# Bakelite_Interface_Board_v1_1.net
KiCad netlist of a schematic drawn in EAGLE
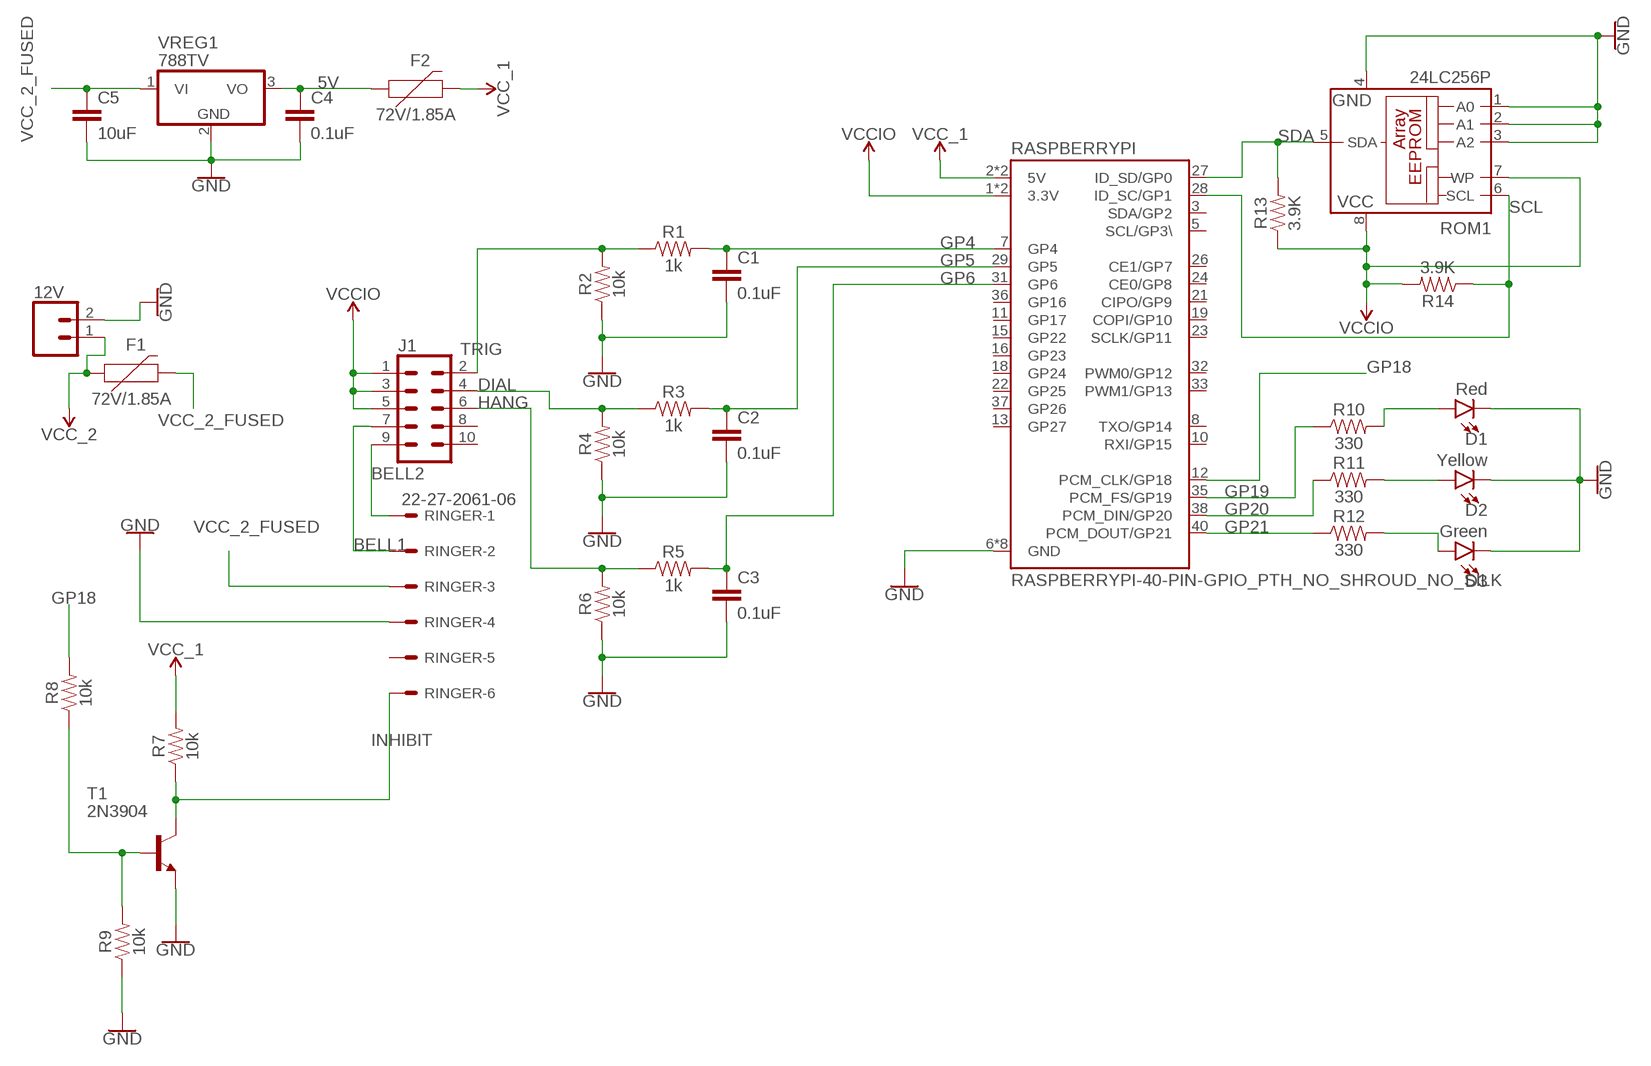
[diagram p0: schematic, sheet 1]

(export (version "E")
  (design (tool "Eeschema 10.0.6"))
  (components
    (comp (ref "12V")
      (value "CONN_025MM")
      (footprint "eagle-import:SCREWTERMINAL-5MM-2")
      (libsource (lib "eagle-import") (part "CONN_025MM"))
    )
    (comp (ref "C1")
      (value "0.1uF")
      (footprint "eagle-import:CAP-PTH-SMALL-KIT")
      (libsource (lib "eagle-import") (part "0.1UF-KIT-EZ-50V-20%"))
    )
    (comp (ref "C2")
      (value "0.1uF")
      (footprint "eagle-import:CAP-PTH-SMALL-KIT")
      (libsource (lib "eagle-import") (part "0.1UF-KIT-EZ-50V-20%"))
    )
    (comp (ref "C3")
      (value "0.1uF")
      (footprint "eagle-import:CAP-PTH-SMALL-KIT")
      (libsource (lib "eagle-import") (part "0.1UF-KIT-EZ-50V-20%"))
    )
    (comp (ref "C4")
      (value "0.1uF")
      (footprint "eagle-import:CAP-PTH-SMALL-KIT")
      (libsource (lib "eagle-import") (part "0.1UF-KIT-EZ-50V-20%"))
    )
    (comp (ref "C5")
      (value "10uF")
      (footprint "eagle-import:CAP-PTH-SMALL-KIT")
      (libsource (lib "eagle-import") (part "0.1UF-KIT-EZ-50V-20%"))
    )
    (comp (ref "D1")
      (value "Red")
      (footprint "eagle-import:LED_5MM")
      (libsource (lib "eagle-import") (part "LED5MM"))
    )
    (comp (ref "D2")
      (value "Yellow")
      (footprint "eagle-import:LED_5MM")
      (libsource (lib "eagle-import") (part "LED5MM"))
    )
    (comp (ref "D3")
      (value "Green")
      (footprint "eagle-import:LED_5MM")
      (libsource (lib "eagle-import") (part "LED5MM"))
    )
    (comp (ref "F1")
      (value "72V/1.85A")
      (footprint "eagle-import:PTH")
      (libsource (lib "eagle-import") (part "PPTC_PTH"))
    )
    (comp (ref "F2")
      (value "72V/1.85A")
      (footprint "eagle-import:PTH")
      (libsource (lib "eagle-import") (part "PPTC_PTH"))
    )
    (comp (ref "J1")
      (value "CONN_05X2PTH")
      (footprint "eagle-import:2X5")
      (libsource (lib "eagle-import") (part "CONN_05X2PTH"))
    )
    (comp (ref "R1")
      (value "1k")
      (footprint "eagle-import:AXIAL-0.3")
      (libsource (lib "eagle-import") (part "1KOHM-HORIZ-1/4W-5%"))
    )
    (comp (ref "R2")
      (value "10k")
      (footprint "eagle-import:AXIAL-0.3")
      (libsource (lib "eagle-import") (part "10KOHM-HORIZ-1/4W-5%"))
    )
    (comp (ref "R3")
      (value "1k")
      (footprint "eagle-import:AXIAL-0.3")
      (libsource (lib "eagle-import") (part "1KOHM-HORIZ-1/4W-5%"))
    )
    (comp (ref "R4")
      (value "10k")
      (footprint "eagle-import:AXIAL-0.3")
      (libsource (lib "eagle-import") (part "10KOHM-HORIZ-1/4W-5%"))
    )
    (comp (ref "R5")
      (value "1k")
      (footprint "eagle-import:AXIAL-0.3")
      (libsource (lib "eagle-import") (part "1KOHM-HORIZ-1/4W-5%"))
    )
    (comp (ref "R6")
      (value "10k")
      (footprint "eagle-import:AXIAL-0.3")
      (libsource (lib "eagle-import") (part "10KOHM-HORIZ-1/4W-5%"))
    )
    (comp (ref "R7")
      (value "10k")
      (footprint "eagle-import:AXIAL-0.3")
      (libsource (lib "eagle-import") (part "10KOHM-HORIZ-1/4W-5%"))
    )
    (comp (ref "R8")
      (value "10k")
      (footprint "eagle-import:AXIAL-0.3")
      (libsource (lib "eagle-import") (part "10KOHM-HORIZ-1/4W-5%"))
    )
    (comp (ref "R9")
      (value "10k")
      (footprint "eagle-import:AXIAL-0.3")
      (libsource (lib "eagle-import") (part "10KOHM-HORIZ-1/4W-5%"))
    )
    (comp (ref "R10")
      (value "330")
      (footprint "eagle-import:AXIAL-0.3")
      (libsource (lib "eagle-import") (part "330OHM-HORIZ-1/10W-5%"))
    )
    (comp (ref "R11")
      (value "330")
      (footprint "eagle-import:AXIAL-0.3")
      (libsource (lib "eagle-import") (part "330OHM-HORIZ-1/10W-5%"))
    )
    (comp (ref "R12")
      (value "330")
      (footprint "eagle-import:AXIAL-0.3")
      (libsource (lib "eagle-import") (part "330OHM-HORIZ-1/10W-5%"))
    )
    (comp (ref "R13")
      (value "3.9K")
      (footprint "eagle-import:AXIAL-0.3")
      (libsource (lib "eagle-import") (part "RESISTORAXIAL-0.3"))
    )
    (comp (ref "R14")
      (value "3.9K")
      (footprint "eagle-import:AXIAL-0.3")
      (libsource (lib "eagle-import") (part "RESISTORAXIAL-0.3"))
    )
    (comp (ref "RASPBERRYPI")
      (value "RASPBERRYPI-40-PIN-GPIO_PTH_NO_SHROUD_NO_SILK")
      (footprint "eagle-import:2X20_NOSILK")
      (libsource (lib "eagle-import") (part "RASPBERRYPI-40-PIN-GPIO_PTH_NO_SHROUD_NO_SILK"))
    )
    (comp (ref "RINGER")
      (value "22-27-2061-06")
      (footprint "eagle-import:6410-06")
      (fields (field (name "MF") "MOLEX"))
      (libsource (lib "eagle-import") (part "22-?-0627-2061"))
    )
    (comp (ref "ROM1")
      (value "24LC256P")
      (footprint "eagle-import:DIL8")
      (fields (field (name "MF") "MICROCHIP") (field (name "MPN") "24LC256-E/P"))
      (libsource (lib "eagle-import") (part "24PLC256"))
    )
    (comp (ref "T1")
      (value "2N3904")
      (footprint "eagle-import:TO92")
      (libsource (lib "eagle-import") (part "2N3904"))
    )
    (comp (ref "VREG1")
      (value "788TV")
      (footprint "eagle-import:TO220V")
      (libsource (lib "eagle-import") (part "78TV8"))
    )
  )
  (nets
    (net (code "1") (name "/5V") (class "Default")
      (node (ref "C4") (pin "1") (pinfunction "1_1") (pintype "passive"))
      (node (ref "F2") (pin "P$1") (pinfunction "1_P$1") (pintype "bidirectional"))
      (node (ref "VREG1") (pin "3") (pinfunction "VO_3") (pintype "passive"))
    )
    (net (code "2") (name "/BELL1") (class "Default")
      (node (ref "J1") (pin "7") (pinfunction "7_7") (pintype "passive"))
      (node (ref "RINGER") (pin "2") (pinfunction "S_2") (pintype "passive"))
    )
    (net (code "3") (name "/BELL2") (class "Default")
      (node (ref "J1") (pin "9") (pinfunction "9_9") (pintype "passive"))
      (node (ref "RINGER") (pin "1") (pinfunction "S_1") (pintype "passive"))
    )
    (net (code "4") (name "/DIAL") (class "Default")
      (node (ref "J1") (pin "4") (pinfunction "4_4") (pintype "passive"))
      (node (ref "R3") (pin "P$1") (pinfunction "1_P$1") (pintype "passive"))
      (node (ref "R4") (pin "P$2") (pinfunction "2_P$2") (pintype "passive"))
    )
    (net (code "5") (name "/GP4") (class "Default")
      (node (ref "C1") (pin "1") (pinfunction "1_1") (pintype "passive"))
      (node (ref "R1") (pin "P$2") (pinfunction "2_P$2") (pintype "passive"))
      (node (ref "RASPBERRYPI") (pin "7") (pinfunction "GP4_7") (pintype "bidirectional"))
    )
    (net (code "6") (name "/GP5") (class "Default")
      (node (ref "C2") (pin "1") (pinfunction "1_1") (pintype "passive"))
      (node (ref "R3") (pin "P$2") (pinfunction "2_P$2") (pintype "passive"))
      (node (ref "RASPBERRYPI") (pin "29") (pinfunction "GP5_29") (pintype "bidirectional"))
    )
    (net (code "7") (name "/GP6") (class "Default")
      (node (ref "C3") (pin "1") (pinfunction "1_1") (pintype "passive"))
      (node (ref "R5") (pin "P$2") (pinfunction "2_P$2") (pintype "passive"))
      (node (ref "RASPBERRYPI") (pin "31") (pinfunction "GP6_31") (pintype "bidirectional"))
    )
    (net (code "8") (name "/GP18") (class "Default")
      (node (ref "R8") (pin "P$2") (pinfunction "2_P$2") (pintype "passive"))
      (node (ref "RASPBERRYPI") (pin "12") (pinfunction "PCM_CLK/GP18_12") (pintype "bidirectional"))
    )
    (net (code "9") (name "/GP19") (class "Default")
      (node (ref "R10") (pin "P$1") (pinfunction "1_P$1") (pintype "passive"))
      (node (ref "RASPBERRYPI") (pin "35") (pinfunction "PCM_FS/GP19_35") (pintype "bidirectional"))
    )
    (net (code "10") (name "/GP20") (class "Default")
      (node (ref "R11") (pin "P$1") (pinfunction "1_P$1") (pintype "passive"))
      (node (ref "RASPBERRYPI") (pin "38") (pinfunction "PCM_DIN/GP20_38") (pintype "bidirectional"))
    )
    (net (code "11") (name "/GP21") (class "Default")
      (node (ref "R12") (pin "P$1") (pinfunction "1_P$1") (pintype "passive"))
      (node (ref "RASPBERRYPI") (pin "40") (pinfunction "PCM_DOUT/GP21_40") (pintype "bidirectional"))
    )
    (net (code "12") (name "/HANG") (class "Default")
      (node (ref "J1") (pin "6") (pinfunction "6_6") (pintype "passive"))
      (node (ref "R5") (pin "P$1") (pinfunction "1_P$1") (pintype "passive"))
      (node (ref "R6") (pin "P$2") (pinfunction "2_P$2") (pintype "passive"))
    )
    (net (code "13") (name "/INHIBIT") (class "Default")
      (node (ref "R7") (pin "P$1") (pinfunction "1_P$1") (pintype "passive"))
      (node (ref "RINGER") (pin "6") (pinfunction "S_6") (pintype "passive"))
      (node (ref "T1") (pin "1") (pinfunction "C_1") (pintype "passive"))
    )
    (net (code "14") (name "/SCL") (class "Default")
      (node (ref "R14") (pin "P$1") (pinfunction "1_P$1") (pintype "passive"))
      (node (ref "RASPBERRYPI") (pin "28") (pinfunction "ID_SC/GP1_28") (pintype "bidirectional"))
      (node (ref "ROM1") (pin "6") (pinfunction "SCL_6") (pintype "input"))
    )
    (net (code "15") (name "/SDA") (class "Default")
      (node (ref "R13") (pin "P$2") (pinfunction "2_P$2") (pintype "passive"))
      (node (ref "RASPBERRYPI") (pin "27") (pinfunction "ID_SD/GP0_27") (pintype "bidirectional"))
      (node (ref "ROM1") (pin "5") (pinfunction "SDA_5") (pintype "bidirectional"))
    )
    (net (code "16") (name "/TRIG") (class "Default")
      (node (ref "J1") (pin "2") (pinfunction "2_2") (pintype "passive"))
      (node (ref "R1") (pin "P$1") (pinfunction "1_P$1") (pintype "passive"))
      (node (ref "R2") (pin "P$2") (pinfunction "2_P$2") (pintype "passive"))
    )
    (net (code "17") (name "/VCC_2_FUSED") (class "Default")
      (node (ref "C5") (pin "1") (pinfunction "1_1") (pintype "passive"))
      (node (ref "F1") (pin "P$2") (pinfunction "2_P$2") (pintype "bidirectional"))
      (node (ref "RINGER") (pin "3") (pinfunction "S_3") (pintype "passive"))
      (node (ref "VREG1") (pin "1") (pinfunction "VI_1") (pintype "input"))
    )
    (net (code "18") (name "GND") (class "Default")
      (node (ref "12V") (pin "2") (pinfunction "2_2") (pintype "passive"))
      (node (ref "C1") (pin "2") (pinfunction "2_2") (pintype "passive"))
      (node (ref "C2") (pin "2") (pinfunction "2_2") (pintype "passive"))
      (node (ref "C3") (pin "2") (pinfunction "2_2") (pintype "passive"))
      (node (ref "C4") (pin "2") (pinfunction "2_2") (pintype "passive"))
      (node (ref "C5") (pin "2") (pinfunction "2_2") (pintype "passive"))
      (node (ref "D1") (pin "K") (pinfunction "C_K") (pintype "passive"))
      (node (ref "D2") (pin "K") (pinfunction "C_K") (pintype "passive"))
      (node (ref "D3") (pin "K") (pinfunction "C_K") (pintype "passive"))
      (node (ref "R2") (pin "P$1") (pinfunction "1_P$1") (pintype "passive"))
      (node (ref "R4") (pin "P$1") (pinfunction "1_P$1") (pintype "passive"))
      (node (ref "R6") (pin "P$1") (pinfunction "1_P$1") (pintype "passive"))
      (node (ref "R9") (pin "P$1") (pinfunction "1_P$1") (pintype "passive"))
      (node (ref "RASPBERRYPI") (pin "14") (pinfunction "GND_14") (pintype "power_in"))
      (node (ref "RASPBERRYPI") (pin "20") (pinfunction "GND_20") (pintype "power_in"))
      (node (ref "RASPBERRYPI") (pin "25") (pinfunction "GND_25") (pintype "power_in"))
      (node (ref "RASPBERRYPI") (pin "30") (pinfunction "GND_30") (pintype "power_in"))
      (node (ref "RASPBERRYPI") (pin "34") (pinfunction "GND_34") (pintype "power_in"))
      (node (ref "RASPBERRYPI") (pin "39") (pinfunction "GND_39") (pintype "power_in"))
      (node (ref "RASPBERRYPI") (pin "6") (pinfunction "GND_6") (pintype "power_in"))
      (node (ref "RASPBERRYPI") (pin "9") (pinfunction "GND_9") (pintype "power_in"))
      (node (ref "RINGER") (pin "4") (pinfunction "S_4") (pintype "passive"))
      (node (ref "ROM1") (pin "1") (pinfunction "A0_1") (pintype "input"))
      (node (ref "ROM1") (pin "2") (pinfunction "A1_2") (pintype "input"))
      (node (ref "ROM1") (pin "3") (pinfunction "A2_3") (pintype "input"))
      (node (ref "ROM1") (pin "4") (pinfunction "GND_4") (pintype "power_in"))
      (node (ref "T1") (pin "3") (pinfunction "E_3") (pintype "passive"))
      (node (ref "VREG1") (pin "2") (pinfunction "GND_2") (pintype "passive"))
    )
    (net (code "19") (name "Net-(R8-1)") (class "Default")
      (node (ref "R8") (pin "P$1") (pinfunction "1_P$1") (pintype "passive"))
      (node (ref "R9") (pin "P$2") (pinfunction "2_P$2") (pintype "passive"))
      (node (ref "T1") (pin "2") (pinfunction "B_2") (pintype "passive"))
    )
    (net (code "20") (name "Net-(R10-2)") (class "Default")
      (node (ref "D1") (pin "A") (pinfunction "A_A") (pintype "passive"))
      (node (ref "R10") (pin "P$2") (pinfunction "2_P$2") (pintype "passive"))
    )
    (net (code "21") (name "Net-(R11-2)") (class "Default")
      (node (ref "D2") (pin "A") (pinfunction "A_A") (pintype "passive"))
      (node (ref "R11") (pin "P$2") (pinfunction "2_P$2") (pintype "passive"))
    )
    (net (code "22") (name "Net-(R12-2)") (class "Default")
      (node (ref "D3") (pin "A") (pinfunction "A_A") (pintype "passive"))
      (node (ref "R12") (pin "P$2") (pinfunction "2_P$2") (pintype "passive"))
    )
    (net (code "23") (name "VCCIO") (class "Default")
      (node (ref "J1") (pin "1") (pinfunction "1_1") (pintype "passive"))
      (node (ref "J1") (pin "3") (pinfunction "3_3") (pintype "passive"))
      (node (ref "J1") (pin "5") (pinfunction "5_5") (pintype "passive"))
      (node (ref "R13") (pin "P$1") (pinfunction "1_P$1") (pintype "passive"))
      (node (ref "R14") (pin "P$2") (pinfunction "2_P$2") (pintype "passive"))
      (node (ref "RASPBERRYPI") (pin "1") (pinfunction "3.3V_1") (pintype "power_in"))
      (node (ref "RASPBERRYPI") (pin "17") (pinfunction "3.3V_17") (pintype "power_in"))
      (node (ref "ROM1") (pin "7") (pinfunction "WP_7") (pintype "input"))
      (node (ref "ROM1") (pin "8") (pinfunction "VCC_8") (pintype "power_in"))
    )
    (net (code "24") (name "VCC_1") (class "Default")
      (node (ref "F2") (pin "P$2") (pinfunction "2_P$2") (pintype "bidirectional"))
      (node (ref "R7") (pin "P$2") (pinfunction "2_P$2") (pintype "passive"))
      (node (ref "RASPBERRYPI") (pin "2") (pinfunction "5V_2") (pintype "power_in"))
      (node (ref "RASPBERRYPI") (pin "4") (pinfunction "5V_4") (pintype "power_in"))
    )
    (net (code "25") (name "VCC_2") (class "Default")
      (node (ref "12V") (pin "1") (pinfunction "1_1") (pintype "passive"))
      (node (ref "F1") (pin "P$1") (pinfunction "1_P$1") (pintype "bidirectional"))
    )
    (net (code "26") (name "unconnected-(J1-Pad8)") (class "Default")
      (node (ref "J1") (pin "8") (pinfunction "8_8") (pintype "passive"))
    )
    (net (code "27") (name "unconnected-(J1-Pad10)") (class "Default")
      (node (ref "J1") (pin "10") (pinfunction "10_10") (pintype "passive"))
    )
    (net (code "28") (name "unconnected-(RASPBERRYPI-CE0{slash}GP8-Pad24)") (class "Default")
      (node (ref "RASPBERRYPI") (pin "24") (pinfunction "CE0/GP8_24") (pintype "output"))
    )
    (net (code "29") (name "unconnected-(RASPBERRYPI-CE1{slash}GP7-Pad26)") (class "Default")
      (node (ref "RASPBERRYPI") (pin "26") (pinfunction "CE1/GP7_26") (pintype "output"))
    )
    (net (code "30") (name "unconnected-(RASPBERRYPI-CIPO{slash}GP9-Pad21)") (class "Default")
      (node (ref "RASPBERRYPI") (pin "21") (pinfunction "CIPO/GP9_21") (pintype "input"))
    )
    (net (code "31") (name "unconnected-(RASPBERRYPI-COPI{slash}GP10-Pad19)") (class "Default")
      (node (ref "RASPBERRYPI") (pin "19") (pinfunction "COPI/GP10_19") (pintype "output"))
    )
    (net (code "32") (name "unconnected-(RASPBERRYPI-GP16-Pad36)") (class "Default")
      (node (ref "RASPBERRYPI") (pin "36") (pinfunction "GP16_36") (pintype "bidirectional"))
    )
    (net (code "33") (name "unconnected-(RASPBERRYPI-GP17-Pad11)") (class "Default")
      (node (ref "RASPBERRYPI") (pin "11") (pinfunction "GP17_11") (pintype "bidirectional"))
    )
    (net (code "34") (name "unconnected-(RASPBERRYPI-GP22-Pad15)") (class "Default")
      (node (ref "RASPBERRYPI") (pin "15") (pinfunction "GP22_15") (pintype "bidirectional"))
    )
    (net (code "35") (name "unconnected-(RASPBERRYPI-GP23-Pad16)") (class "Default")
      (node (ref "RASPBERRYPI") (pin "16") (pinfunction "GP23_16") (pintype "bidirectional"))
    )
    (net (code "36") (name "unconnected-(RASPBERRYPI-GP24-Pad18)") (class "Default")
      (node (ref "RASPBERRYPI") (pin "18") (pinfunction "GP24_18") (pintype "bidirectional"))
    )
    (net (code "37") (name "unconnected-(RASPBERRYPI-GP25-Pad22)") (class "Default")
      (node (ref "RASPBERRYPI") (pin "22") (pinfunction "GP25_22") (pintype "bidirectional"))
    )
    (net (code "38") (name "unconnected-(RASPBERRYPI-GP26-Pad37)") (class "Default")
      (node (ref "RASPBERRYPI") (pin "37") (pinfunction "GP26_37") (pintype "bidirectional"))
    )
    (net (code "39") (name "unconnected-(RASPBERRYPI-GP27-Pad13)") (class "Default")
      (node (ref "RASPBERRYPI") (pin "13") (pinfunction "GP27_13") (pintype "bidirectional"))
    )
    (net (code "40") (name "unconnected-(RASPBERRYPI-PWM0{slash}GP12-Pad32)") (class "Default")
      (node (ref "RASPBERRYPI") (pin "32") (pinfunction "PWM0/GP12_32") (pintype "bidirectional"))
    )
    (net (code "41") (name "unconnected-(RASPBERRYPI-PWM1{slash}GP13-Pad33)") (class "Default")
      (node (ref "RASPBERRYPI") (pin "33") (pinfunction "PWM1/GP13_33") (pintype "bidirectional"))
    )
    (net (code "42") (name "unconnected-(RASPBERRYPI-RXI{slash}GP15-Pad10)") (class "Default")
      (node (ref "RASPBERRYPI") (pin "10") (pinfunction "RXI/GP15_10") (pintype "input"))
    )
    (net (code "43") (name "unconnected-(RASPBERRYPI-SCLK{slash}GP11-Pad23)") (class "Default")
      (node (ref "RASPBERRYPI") (pin "23") (pinfunction "SCLK/GP11_23") (pintype "output"))
    )
    (net (code "44") (name "unconnected-(RASPBERRYPI-SCL{slash}GP3\\-Pad5)") (class "Default")
      (node (ref "RASPBERRYPI") (pin "5") (pinfunction "SCL/GP3\\_5") (pintype "bidirectional"))
    )
    (net (code "45") (name "unconnected-(RASPBERRYPI-SDA{slash}GP2-Pad3)") (class "Default")
      (node (ref "RASPBERRYPI") (pin "3") (pinfunction "SDA/GP2_3") (pintype "bidirectional"))
    )
    (net (code "46") (name "unconnected-(RASPBERRYPI-TXO{slash}GP14-Pad8)") (class "Default")
      (node (ref "RASPBERRYPI") (pin "8") (pinfunction "TXO/GP14_8") (pintype "output"))
    )
    (net (code "47") (name "unconnected-(RINGERE-S-Pad5)") (class "Default")
      (node (ref "RINGER") (pin "5") (pinfunction "S_5") (pintype "passive"))
    )
  )
)
